# reader.net
KiCad netlist of a schematic drawn in EAGLE
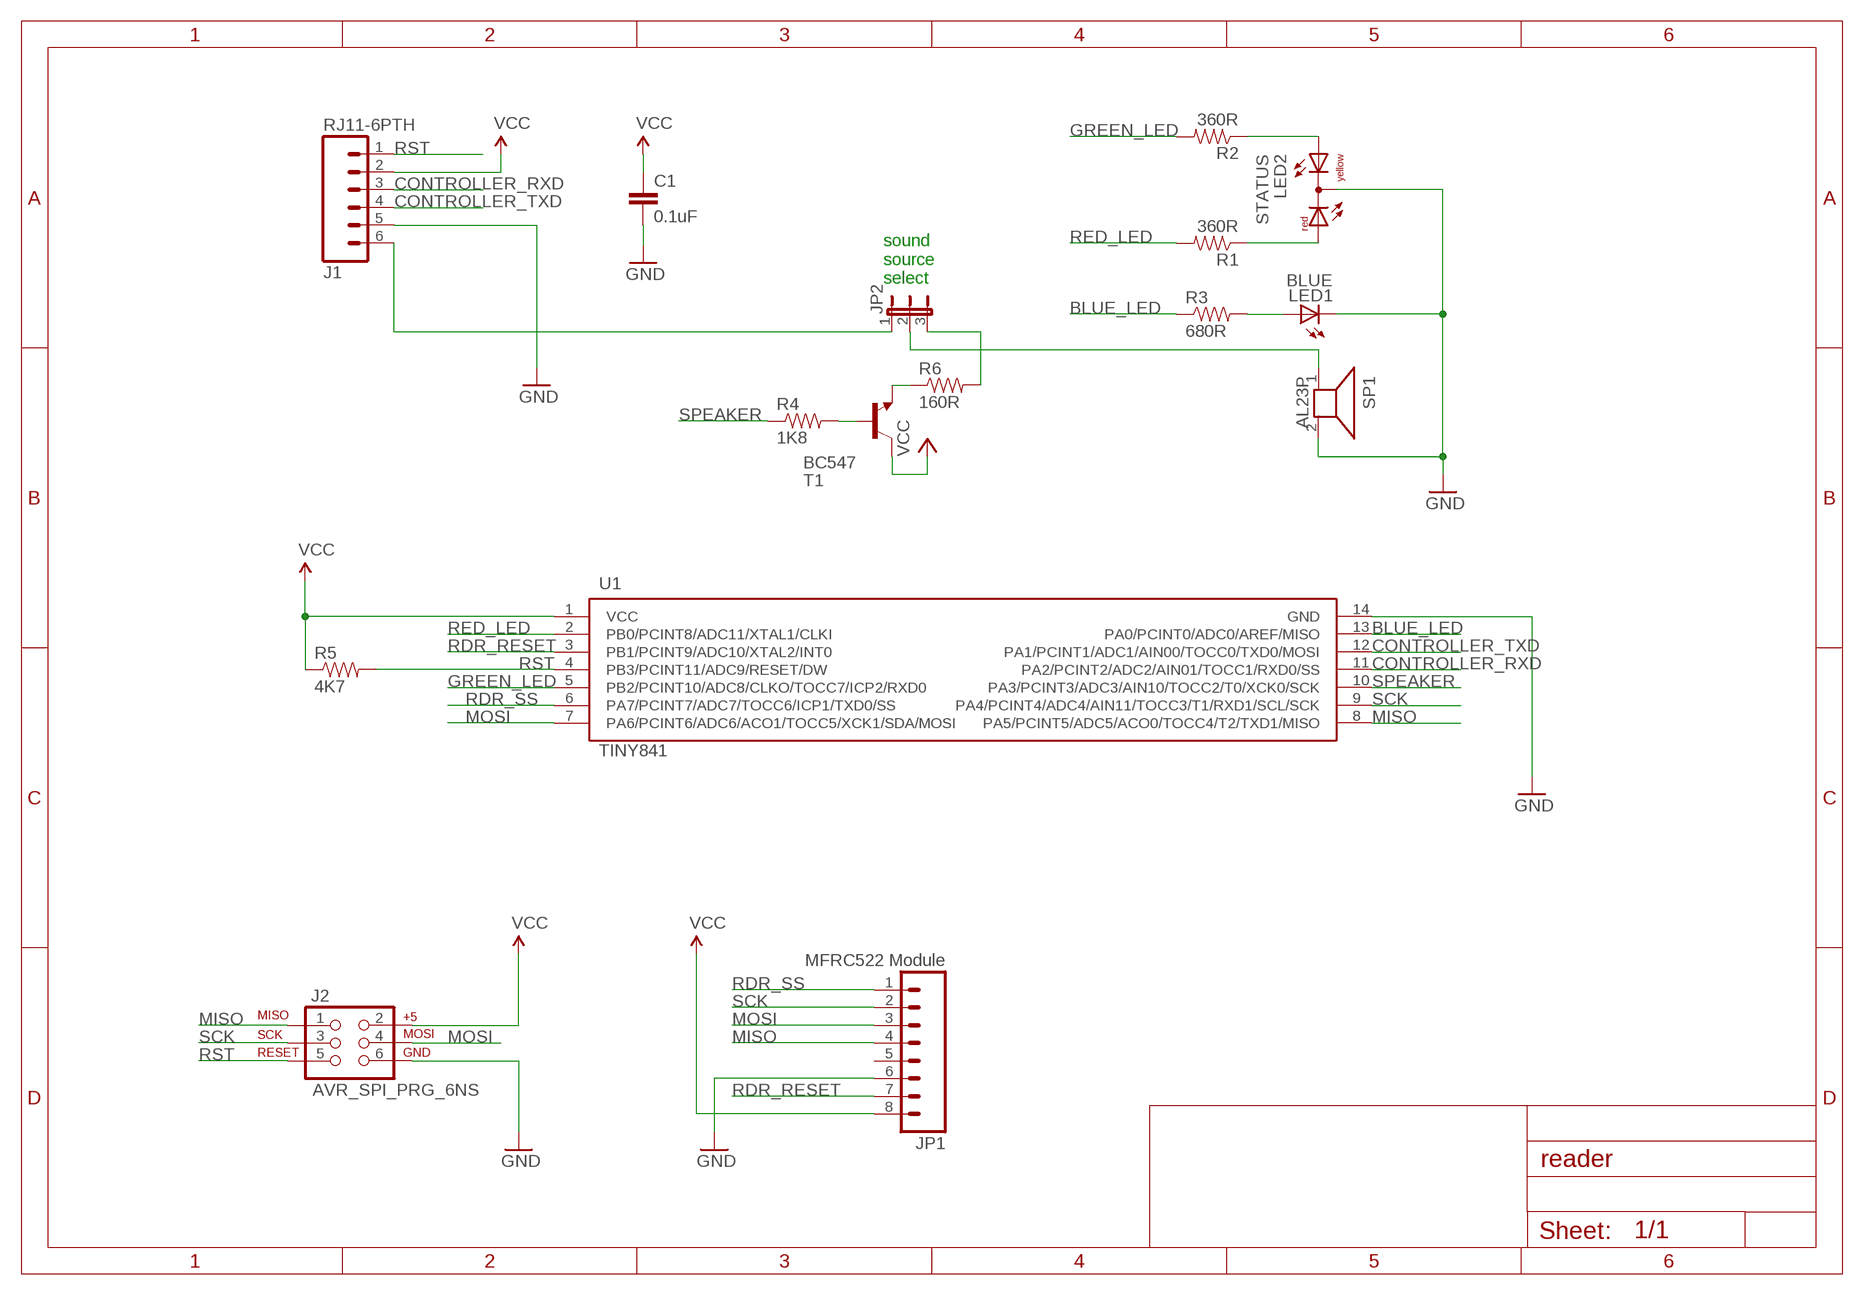
[diagram p0: schematic, sheet 1]

(export (version "E")
  (design (tool "Eeschema 10.0.6"))
  (components
    (comp (ref "C1")
      (value "0.1uF")
      (footprint "eagle-import:CAP-PTH-SMALL-KIT")
      (libsource (lib "eagle-import") (part "0.1UF-50V-20%(PTH)KIT-EZ"))
    )
    (comp (ref "J1")
      (value "RJ11-6PTH")
      (footprint "eagle-import:RJ11-6")
      (libsource (lib "eagle-import") (part "RJ11-6PTH"))
    )
    (comp (ref "J2")
      (value "AVR_SPI_PRG_6NS")
      (footprint "eagle-import:2X3-NS")
      (libsource (lib "eagle-import") (part "AVR_SPI_PRG_6NS"))
    )
    (comp (ref "JP1")
      (value "MFRC522 Module")
      (footprint "eagle-import:1X08")
      (libsource (lib "eagle-import") (part "M081X08"))
    )
    (comp (ref "JP2")
      (value "JP2E")
      (footprint "eagle-import:JP2")
      (libsource (lib "eagle-import") (part "JP2E"))
    )
    (comp (ref "LED1")
      (value "BLUE")
      (footprint "eagle-import:LED3MM")
      (libsource (lib "eagle-import") (part "LED3MM"))
    )
    (comp (ref "LED2")
      (value "STATUS")
      (footprint "eagle-import:DUOLED-C-5MM")
      (libsource (lib "eagle-import") (part "DUOLED-RY-C"))
    )
    (comp (ref "R1")
      (value "360R")
      (footprint "eagle-import:0805")
      (libsource (lib "eagle-import") (part "RESISTOR0805-RES"))
    )
    (comp (ref "R2")
      (value "360R")
      (footprint "eagle-import:0805")
      (libsource (lib "eagle-import") (part "RESISTOR0805-RES"))
    )
    (comp (ref "R3")
      (value "680R")
      (footprint "eagle-import:0805")
      (libsource (lib "eagle-import") (part "RESISTOR0805-RES"))
    )
    (comp (ref "R4")
      (value "1K8")
      (footprint "eagle-import:0805")
      (libsource (lib "eagle-import") (part "RESISTOR0805-RES"))
    )
    (comp (ref "R5")
      (value "4K7")
      (footprint "eagle-import:0805")
      (libsource (lib "eagle-import") (part "RESISTOR0805-RES"))
    )
    (comp (ref "R6")
      (value "160R")
      (footprint "eagle-import:0805")
      (libsource (lib "eagle-import") (part "RESISTOR0805-RES"))
    )
    (comp (ref "SP1")
      (value "AL23P")
      (footprint "eagle-import:AL23P")
      (libsource (lib "eagle-import") (part "AL23P"))
    )
    (comp (ref "T1")
      (value "BC547")
      (footprint "eagle-import:TO92")
      (libsource (lib "eagle-import") (part "BC547"))
    )
    (comp (ref "U1")
      (value "TINY841")
      (footprint "eagle-import:SO14")
      (libsource (lib "eagle-import") (part "TINY841"))
    )
  )
  (nets
    (net (code "1") (name "/BLUE_LED") (class "Default")
      (node (ref "R3") (pin "1") (pinfunction "1_1") (pintype "passive"))
      (node (ref "U1") (pin "13") (pinfunction "PA0/PCINT0/ADC0/AREF/MISO_13") (pintype "bidirectional"))
    )
    (net (code "2") (name "/CONTROLLER_RXD") (class "Default")
      (node (ref "J1") (pin "3") (pinfunction "3_3") (pintype "passive"))
      (node (ref "U1") (pin "11") (pinfunction "PA2/PCINT2/ADC2/AIN01/TOCC1/RXD0/SS_11") (pintype "bidirectional"))
    )
    (net (code "3") (name "/CONTROLLER_TXD") (class "Default")
      (node (ref "J1") (pin "4") (pinfunction "4_4") (pintype "passive"))
      (node (ref "U1") (pin "12") (pinfunction "PA1/PCINT1/ADC1/AIN00/TOCC0/TXD0/MOSI_12") (pintype "bidirectional"))
    )
    (net (code "4") (name "/GREEN_LED") (class "Default")
      (node (ref "R2") (pin "2") (pinfunction "2_2") (pintype "passive"))
      (node (ref "U1") (pin "5") (pinfunction "PB2/PCINT10/ADC8/CLKO/TOCC7/ICP2/RXD0_5") (pintype "bidirectional"))
    )
    (net (code "5") (name "/MISO") (class "Default")
      (node (ref "J2") (pin "1") (pinfunction "1_1") (pintype "passive"))
      (node (ref "JP1") (pin "4") (pinfunction "4_4") (pintype "passive"))
      (node (ref "U1") (pin "8") (pinfunction "PA5/PCINT5/ADC5/ACO0/TOCC4/T2/TXD1/MISO_8") (pintype "bidirectional"))
    )
    (net (code "6") (name "/MOSI") (class "Default")
      (node (ref "J2") (pin "4") (pinfunction "4_4") (pintype "passive"))
      (node (ref "JP1") (pin "3") (pinfunction "3_3") (pintype "passive"))
      (node (ref "U1") (pin "7") (pinfunction "PA6/PCINT6/ADC6/ACO1/TOCC5/XCK1/SDA/MOSI_7") (pintype "bidirectional"))
    )
    (net (code "7") (name "/RDR_RESET") (class "Default")
      (node (ref "JP1") (pin "7") (pinfunction "7_7") (pintype "passive"))
      (node (ref "U1") (pin "3") (pinfunction "PB1/PCINT9/ADC10/XTAL2/INT0_3") (pintype "bidirectional"))
    )
    (net (code "8") (name "/RDR_SS") (class "Default")
      (node (ref "JP1") (pin "1") (pinfunction "1_1") (pintype "passive"))
      (node (ref "U1") (pin "6") (pinfunction "PA7/PCINT7/ADC7/TOCC6/ICP1/TXD0/SS_6") (pintype "bidirectional"))
    )
    (net (code "9") (name "/RED_LED") (class "Default")
      (node (ref "R1") (pin "2") (pinfunction "2_2") (pintype "passive"))
      (node (ref "U1") (pin "2") (pinfunction "PB0/PCINT8/ADC11/XTAL1/CLKI_2") (pintype "bidirectional"))
    )
    (net (code "10") (name "/RST") (class "Default")
      (node (ref "J1") (pin "1") (pinfunction "1_1") (pintype "passive"))
      (node (ref "J2") (pin "5") (pinfunction "5_5") (pintype "passive"))
      (node (ref "R5") (pin "2") (pinfunction "2_2") (pintype "passive"))
      (node (ref "U1") (pin "4") (pinfunction "PB3/PCINT11/ADC9/RESET/DW_4") (pintype "bidirectional"))
    )
    (net (code "11") (name "/SCK") (class "Default")
      (node (ref "J2") (pin "3") (pinfunction "3_3") (pintype "passive"))
      (node (ref "JP1") (pin "2") (pinfunction "2_2") (pintype "passive"))
      (node (ref "U1") (pin "9") (pinfunction "PA4/PCINT4/ADC4/AIN11/TOCC3/T1/RXD1/SCL/SCK_9") (pintype "bidirectional"))
    )
    (net (code "12") (name "/SPEAKER") (class "Default")
      (node (ref "R4") (pin "1") (pinfunction "1_1") (pintype "passive"))
      (node (ref "U1") (pin "10") (pinfunction "PA3/PCINT3/ADC3/AIN10/TOCC2/T0/XCK0/SCK_10") (pintype "bidirectional"))
    )
    (net (code "13") (name "GND") (class "Default")
      (node (ref "C1") (pin "2") (pinfunction "2_2") (pintype "passive"))
      (node (ref "J1") (pin "5") (pinfunction "5_5") (pintype "passive"))
      (node (ref "J2") (pin "6") (pinfunction "6_6") (pintype "passive"))
      (node (ref "JP1") (pin "6") (pinfunction "6_6") (pintype "passive"))
      (node (ref "LED1") (pin "K") (pinfunction "C_K") (pintype "passive"))
      (node (ref "LED2") (pin "C") (pinfunction "C_C") (pintype "passive"))
      (node (ref "SP1") (pin "2") (pinfunction "2_2") (pintype "passive"))
      (node (ref "U1") (pin "14") (pinfunction "GND_14") (pintype "power_in"))
    )
    (net (code "14") (name "Net-(J1-Pad6)") (class "Default")
      (node (ref "J1") (pin "6") (pinfunction "6_6") (pintype "passive"))
      (node (ref "JP2") (pin "1") (pinfunction "1_1") (pintype "passive"))
    )
    (net (code "15") (name "Net-(JP2-Pad2)") (class "Default")
      (node (ref "JP2") (pin "2") (pinfunction "2_2") (pintype "passive"))
      (node (ref "SP1") (pin "1") (pinfunction "1_1") (pintype "passive"))
    )
    (net (code "16") (name "Net-(JP2-Pad3)") (class "Default")
      (node (ref "JP2") (pin "3") (pinfunction "3_3") (pintype "passive"))
      (node (ref "R6") (pin "2") (pinfunction "2_2") (pintype "passive"))
    )
    (net (code "17") (name "Net-(LED1-PadA)") (class "Default")
      (node (ref "LED1") (pin "A") (pinfunction "A_A") (pintype "passive"))
      (node (ref "R3") (pin "2") (pinfunction "2_2") (pintype "passive"))
    )
    (net (code "18") (name "Net-(LED2-AY)") (class "Default")
      (node (ref "LED2") (pin "AX") (pinfunction "AY_AX") (pintype "passive"))
      (node (ref "R2") (pin "1") (pinfunction "1_1") (pintype "passive"))
    )
    (net (code "19") (name "Net-(LED2-PadAR)") (class "Default")
      (node (ref "LED2") (pin "AR") (pinfunction "AR_AR") (pintype "passive"))
      (node (ref "R1") (pin "1") (pinfunction "1_1") (pintype "passive"))
    )
    (net (code "20") (name "Net-(T1-B)") (class "Default")
      (node (ref "R4") (pin "2") (pinfunction "2_2") (pintype "passive"))
      (node (ref "T1") (pin "2") (pinfunction "B_2") (pintype "passive"))
    )
    (net (code "21") (name "Net-(T1-E)") (class "Default")
      (node (ref "R6") (pin "1") (pinfunction "1_1") (pintype "passive"))
      (node (ref "T1") (pin "1") (pinfunction "E_1") (pintype "passive"))
    )
    (net (code "22") (name "VCC") (class "Default")
      (node (ref "C1") (pin "1") (pinfunction "1_1") (pintype "passive"))
      (node (ref "J1") (pin "2") (pinfunction "2_2") (pintype "passive"))
      (node (ref "J2") (pin "2") (pinfunction "2_2") (pintype "passive"))
      (node (ref "JP1") (pin "8") (pinfunction "8_8") (pintype "passive"))
      (node (ref "R5") (pin "1") (pinfunction "1_1") (pintype "passive"))
      (node (ref "T1") (pin "3") (pinfunction "C_3") (pintype "passive"))
      (node (ref "U1") (pin "1") (pinfunction "VCC_1") (pintype "power_in"))
    )
    (net (code "23") (name "unconnected-(JP1-Pad5)") (class "Default")
      (node (ref "JP1") (pin "5") (pinfunction "5_5") (pintype "passive"))
    )
  )
)
